# Own_21700_Board_v1_0_Final_AR.net
KiCad netlist of a schematic drawn in EAGLE
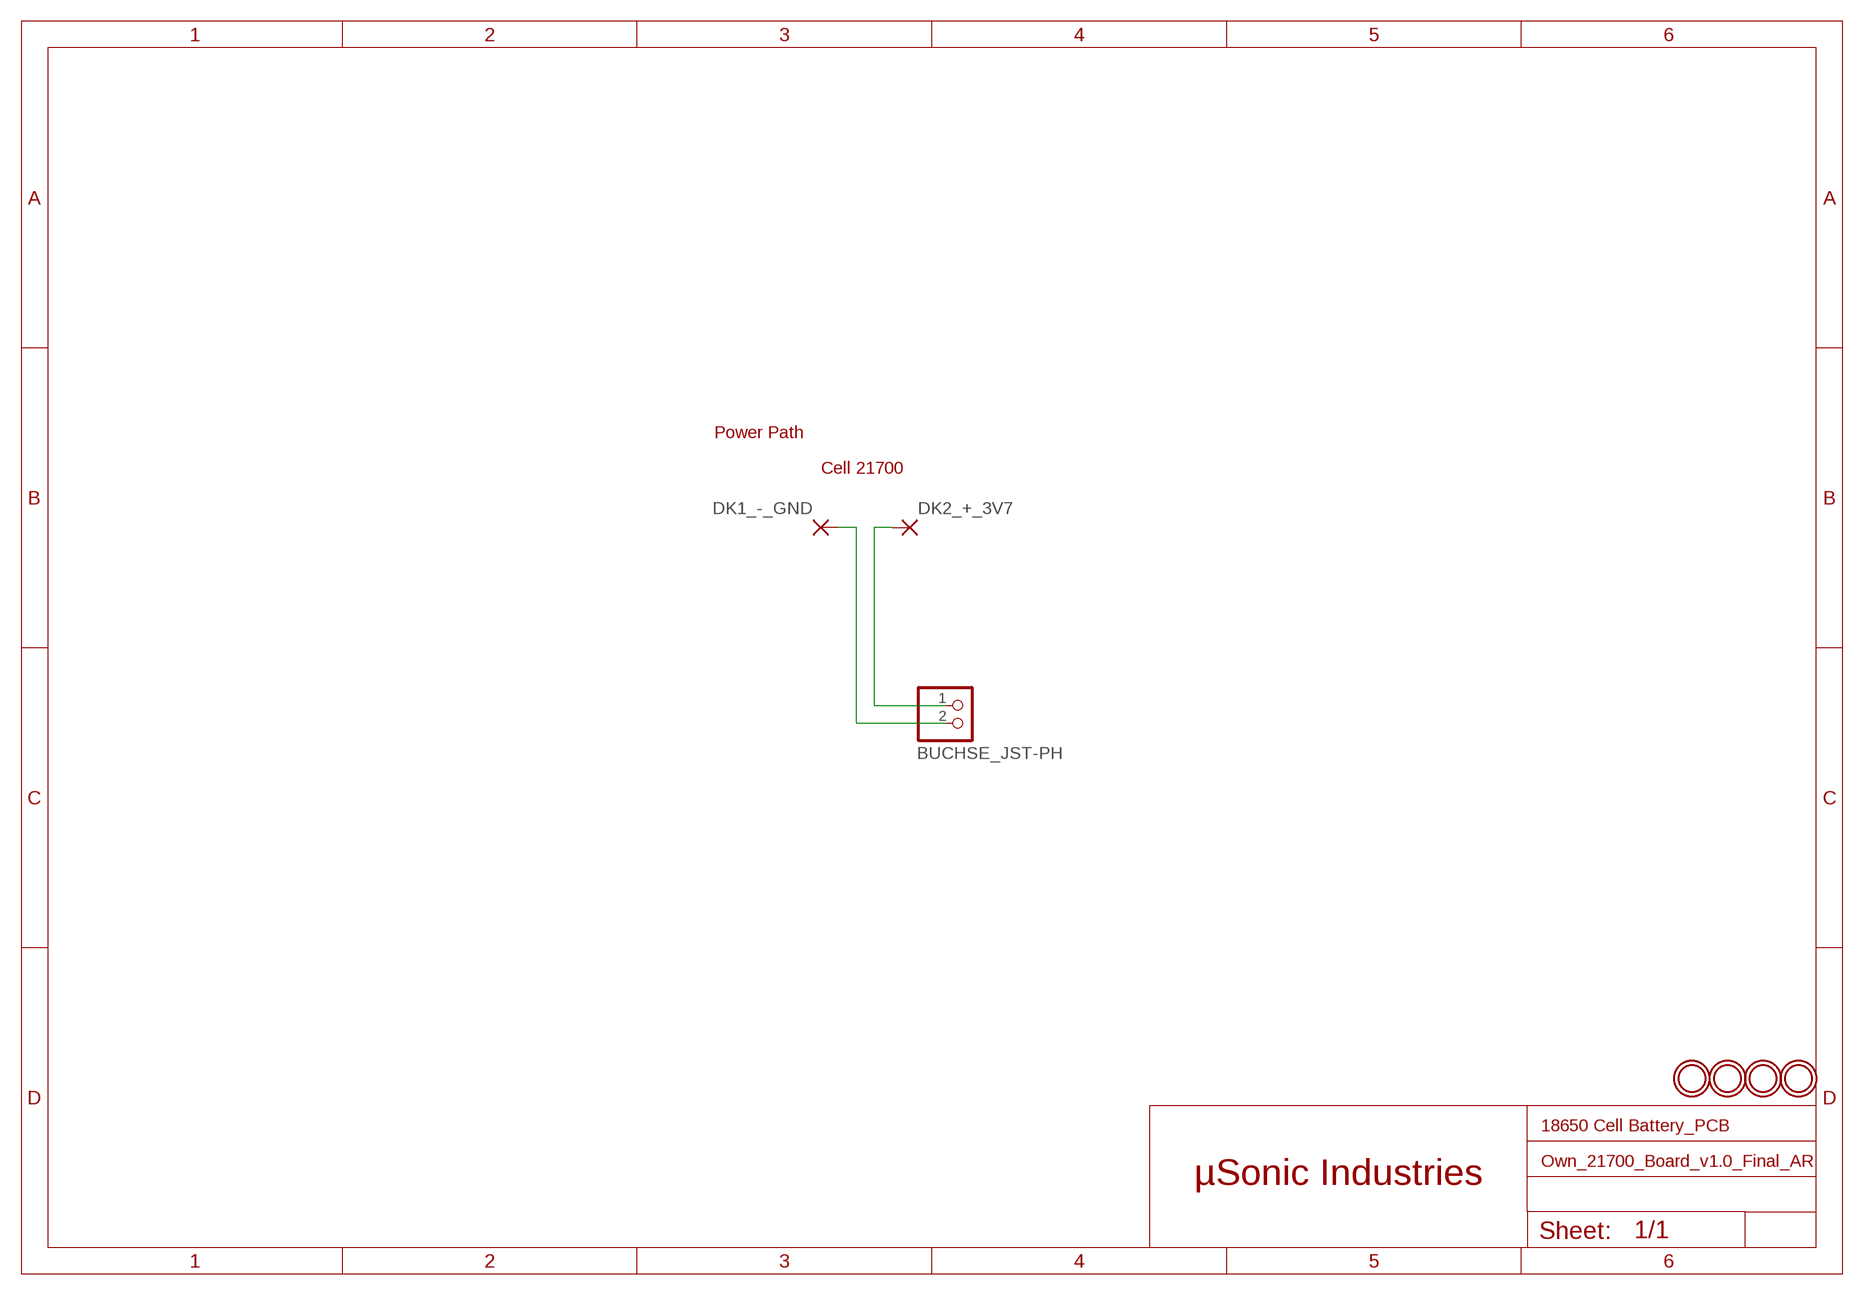
[diagram p0: schematic, sheet 1]

(export (version "E")
  (design (tool "Eeschema 10.0.6"))
  (components
    (comp (ref "BUCHSE_JST-PH")
      (value "JST_2PINOWN")
      (footprint "eagle-import:JST-PH-2-THMOWN")
      (libsource (lib "eagle-import") (part "JST_2PINOWN"))
    )
    (comp (ref "DK1_-_GND")
      (value "3,17/1,3")
      (footprint "eagle-import:3,17_1,3")
      (libsource (lib "eagle-import") (part "3,17/1,3"))
    )
    (comp (ref "DK2_+_3V7")
      (value "3,17/1,3")
      (footprint "eagle-import:3,17_1,3")
      (libsource (lib "eagle-import") (part "3,17/1,3"))
    )
    (comp (ref "U$1")
      (value "MOUNTINGHOLE2.5")
      (footprint "eagle-import:MOUNTINGHOLE_2.5_PLATED")
      (libsource (lib "eagle-import") (part "MOUNTINGHOLE2.5"))
    )
    (comp (ref "U$2")
      (value "MOUNTINGHOLE2.5")
      (footprint "eagle-import:MOUNTINGHOLE_2.5_PLATED")
      (libsource (lib "eagle-import") (part "MOUNTINGHOLE2.5"))
    )
    (comp (ref "U$3")
      (value "MOUNTINGHOLE2.5")
      (footprint "eagle-import:MOUNTINGHOLE_2.5_PLATED")
      (libsource (lib "eagle-import") (part "MOUNTINGHOLE2.5"))
    )
    (comp (ref "U$5")
      (value "MOUNTINGHOLE2.5")
      (footprint "eagle-import:MOUNTINGHOLE_2.5_PLATED")
      (libsource (lib "eagle-import") (part "MOUNTINGHOLE2.5"))
    )
  )
  (nets
    (net (code "1") (name "Net-(BUCHSE_JST-PH-1)") (class "Default")
      (node (ref "BUCHSE_JST-PH") (pin "2") (pinfunction "1_2") (pintype "passive"))
      (node (ref "DK1_-_GND") (pin "1") (pinfunction "P_1") (pintype "passive"))
    )
    (net (code "2") (name "Net-(BUCHSE_JST-PH-2)") (class "Default")
      (node (ref "BUCHSE_JST-PH") (pin "1") (pinfunction "2_1") (pintype "passive"))
      (node (ref "DK2_+_3V7") (pin "1") (pinfunction "P_1") (pintype "passive"))
    )
  )
)
